# SCH_nfc_ing_2025-04-12.net
KiCad netlist of a schematic drawn in EasyEDA
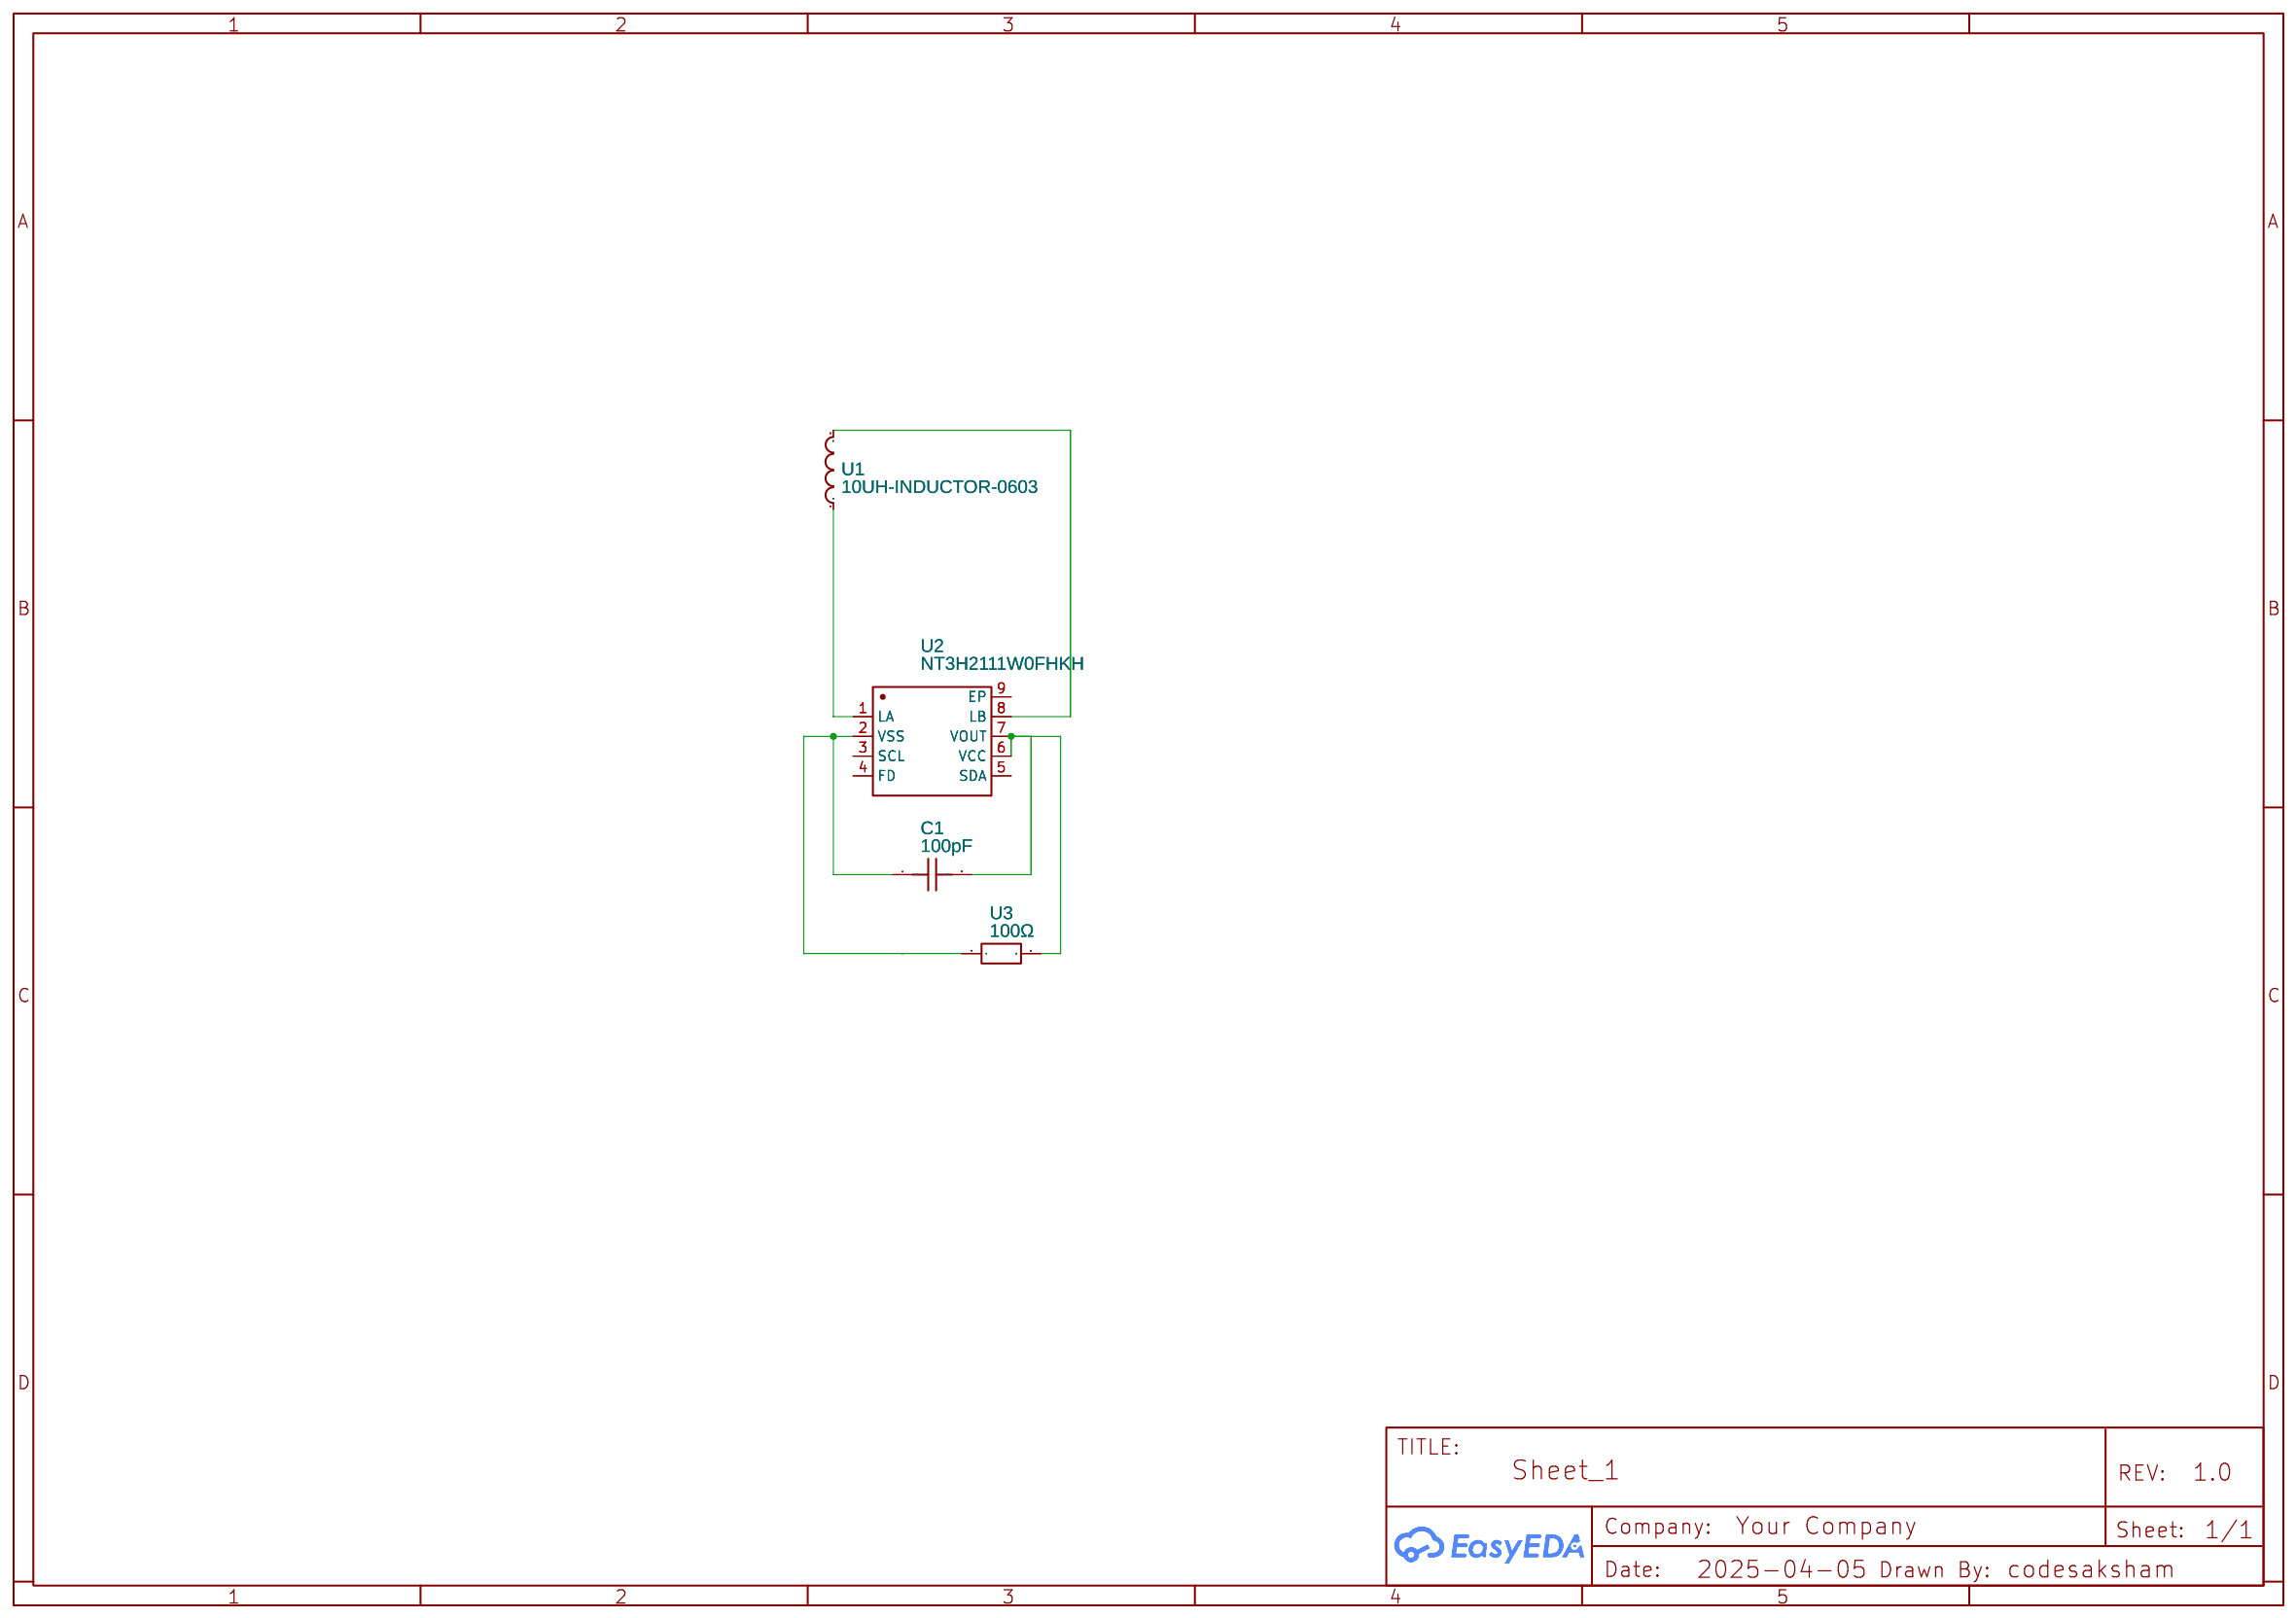
[diagram p0: schematic sheet]

(export (version "E")
  (design (tool "Eeschema 10.0.6"))
  (components
    (comp (ref "C1")
      (value "100pF")
      (fields (field (name "Manufacturer Part") "C0402X6S1A101K020BC") (field (name "Manufacturer") "TDK"))
      (libsource (lib "") (part "C0402X6S1A101K020BC"))
    )
    (comp (ref "U1")
      (value "10UH-INDUCTOR-0603")
      (fields (field (name "Manufacturer Part") "10uH-INDUCTOR-0603"))
      (libsource (lib "") (part "10UH-INDUCTOR-0603"))
    )
    (comp (ref "U2")
      (value "NT3H2111W0FHKH")
      (fields (field (name "Manufacturer") "NXP(恩智浦)"))
      (libsource (lib "") (part "NT3H2111W0FHKH"))
    )
    (comp (ref "U3")
      (value "100Ω")
      (fields
        (field (name "Manufacturer Part") "M55342H03B100DRT5")
        (field (name "Manufacturer") "VISHAY(威世)")
      )
      (libsource (lib "") (part "M55342H03B100DRT5"))
    )
  )
  (nets
    (net (code "1") (name "Net-(U2-LA)") (class "Default")
      (node (ref "U1") (pin "1") (pinfunction "1_1") (pintype "unspecified"))
      (node (ref "U2") (pin "1") (pinfunction "LA_1") (pintype "unspecified"))
    )
    (net (code "2") (name "Net-(U2-LB)") (class "Default")
      (node (ref "U1") (pin "2") (pinfunction "2_2") (pintype "unspecified"))
      (node (ref "U2") (pin "8") (pinfunction "LB_8") (pintype "unspecified"))
    )
    (net (code "3") (name "Net-(U2-VCC)") (class "Default")
      (node (ref "C1") (pin "2") (pinfunction "2_2") (pintype "unspecified"))
      (node (ref "U2") (pin "6") (pinfunction "VCC_6") (pintype "unspecified"))
      (node (ref "U2") (pin "7") (pinfunction "VOUT_7") (pintype "unspecified"))
      (node (ref "U3") (pin "2") (pinfunction "2_2") (pintype "unspecified"))
    )
    (net (code "4") (name "Net-(U2-VSS)") (class "Default")
      (node (ref "C1") (pin "1") (pinfunction "1_1") (pintype "unspecified"))
      (node (ref "U2") (pin "2") (pinfunction "VSS_2") (pintype "unspecified"))
      (node (ref "U3") (pin "1") (pinfunction "1_1") (pintype "unspecified"))
    )
    (net (code "5") (name "unconnected-(U2-EP-Pad9)") (class "Default")
      (node (ref "U2") (pin "9") (pinfunction "EP_9") (pintype "unspecified"))
    )
    (net (code "6") (name "unconnected-(U2-FD-Pad4)") (class "Default")
      (node (ref "U2") (pin "4") (pinfunction "FD_4") (pintype "unspecified"))
    )
    (net (code "7") (name "unconnected-(U2-SCL-Pad3)") (class "Default")
      (node (ref "U2") (pin "3") (pinfunction "SCL_3") (pintype "unspecified"))
    )
    (net (code "8") (name "unconnected-(U2-SDA-Pad5)") (class "Default")
      (node (ref "U2") (pin "5") (pinfunction "SDA_5") (pintype "unspecified"))
    )
  )
)
